# PCB-SSB-4x1.net
KiCad netlist of a schematic drawn in EAGLE
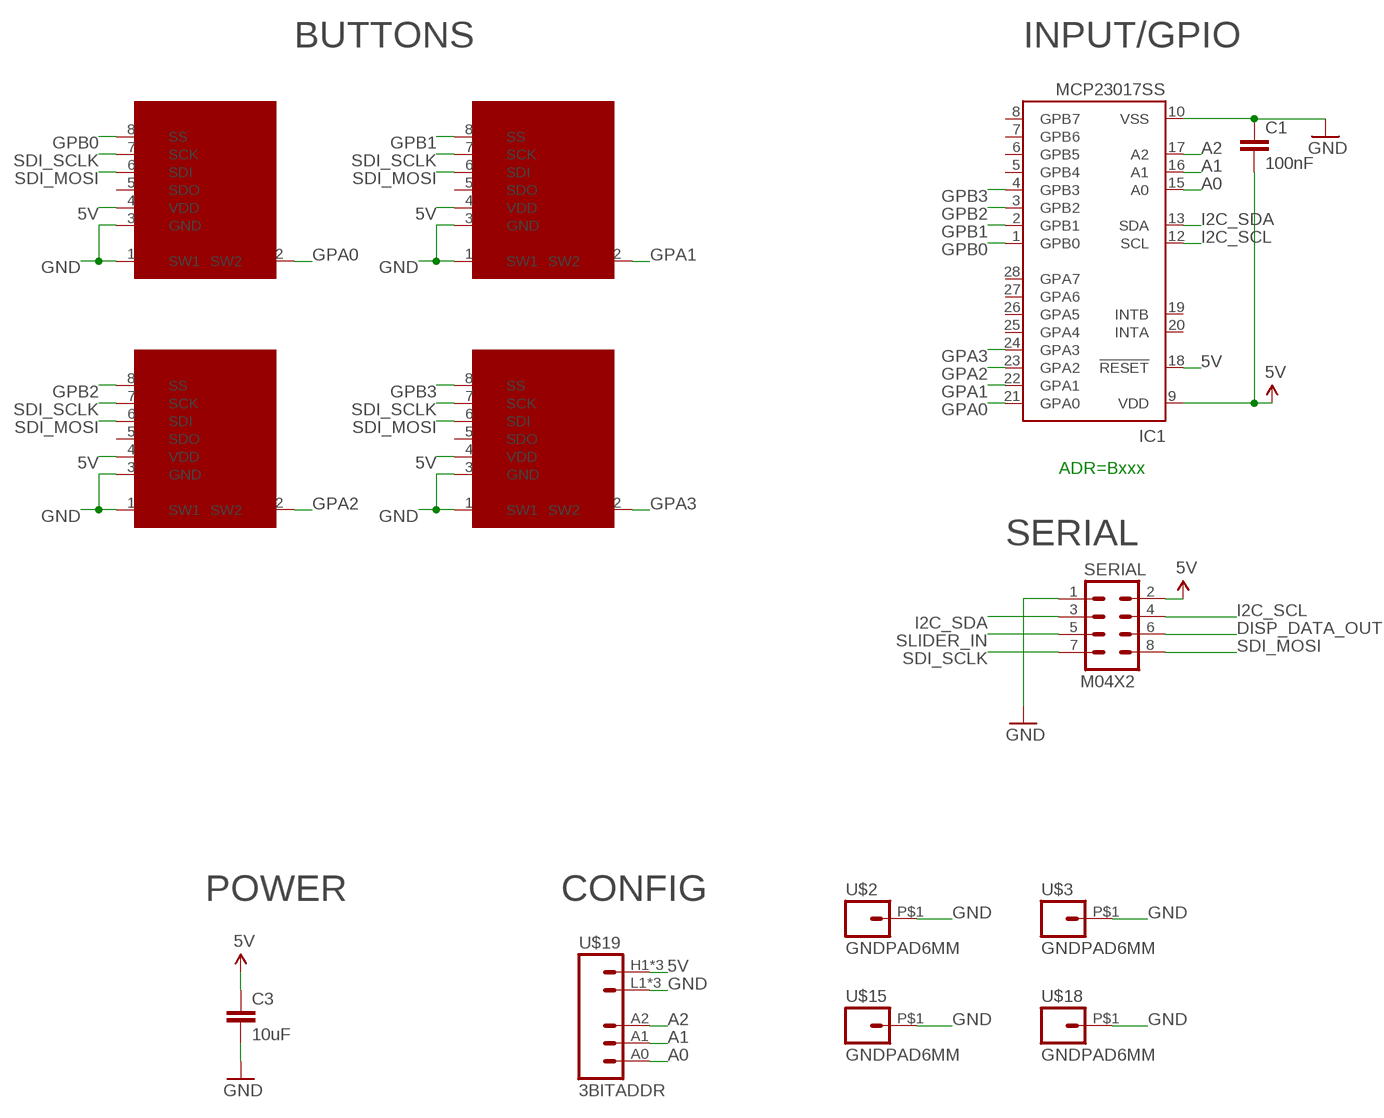
[diagram p0: schematic, sheet 1]

(export (version "E")
  (design (tool "Eeschema 10.0.6"))
  (components
    (comp (ref "C1")
      (value "100nF")
      (footprint "eagle-import:0603-CAP")
      (libsource (lib "eagle-import") (part "CAP0603-CAP"))
    )
    (comp (ref "C3")
      (value "10uF")
      (footprint "eagle-import:0805")
      (libsource (lib "eagle-import") (part "CAP0805"))
    )
    (comp (ref "IC1")
      (value "MCP23017SS")
      (footprint "eagle-import:SSOP28")
      (fields
        (field (name "MF") "MICROCHIP")
        (field (name "MPN") "MCP23017-E/SS")
        (field (name "MPN_1") "MCP23017-E/SS")
        (field (name "OC_FARNELL") "1467674")
        (field (name "OC_NEWARK") "31K2960")
      )
      (libsource (lib "eagle-import") (part "MCP23017SS"))
    )
    (comp (ref "SERIAL")
      (value "M04X2")
      (footprint "eagle-import:2X4")
      (libsource (lib "eagle-import") (part "M04X2"))
    )
    (comp (ref "SSW1")
      (value "SMART_SWITCHSMART_SWITCH_8PIN")
      (footprint "eagle-import:SMART_SWITCH")
      (libsource (lib "eagle-import") (part "SMART_SWITCHSMART_SWITCH_8PIN"))
    )
    (comp (ref "SSW2")
      (value "SMART_SWITCHSMART_SWITCH_8PIN")
      (footprint "eagle-import:SMART_SWITCH")
      (libsource (lib "eagle-import") (part "SMART_SWITCHSMART_SWITCH_8PIN"))
    )
    (comp (ref "SSW3")
      (value "SMART_SWITCHSMART_SWITCH_8PIN")
      (footprint "eagle-import:SMART_SWITCH")
      (libsource (lib "eagle-import") (part "SMART_SWITCHSMART_SWITCH_8PIN"))
    )
    (comp (ref "SSW4")
      (value "SMART_SWITCHSMART_SWITCH_8PIN")
      (footprint "eagle-import:SMART_SWITCH")
      (libsource (lib "eagle-import") (part "SMART_SWITCHSMART_SWITCH_8PIN"))
    )
    (comp (ref "U$2")
      (value "GNDPAD6MM")
      (footprint "eagle-import:3.2MMPAD6MM")
      (libsource (lib "eagle-import") (part "GNDPAD6MM"))
    )
    (comp (ref "U$3")
      (value "GNDPAD6MM")
      (footprint "eagle-import:3.2MMPAD6MM")
      (libsource (lib "eagle-import") (part "GNDPAD6MM"))
    )
    (comp (ref "U$15")
      (value "GNDPAD6MM")
      (footprint "eagle-import:3.2MMPAD6MM")
      (libsource (lib "eagle-import") (part "GNDPAD6MM"))
    )
    (comp (ref "U$18")
      (value "GNDPAD6MM")
      (footprint "eagle-import:3.2MMPAD6MM")
      (libsource (lib "eagle-import") (part "GNDPAD6MM"))
    )
    (comp (ref "U$19")
      (value "3BITADDR")
      (footprint "eagle-import:3BITADDR")
      (libsource (lib "eagle-import") (part "3BITADDR"))
    )
  )
  (nets
    (net (code "1") (name "/A0") (class "Default")
      (node (ref "IC1") (pin "15") (pinfunction "A0_15") (pintype "input"))
      (node (ref "U$19") (pin "A0") (pinfunction "A0_A0") (pintype "passive"))
    )
    (net (code "2") (name "/A1") (class "Default")
      (node (ref "IC1") (pin "16") (pinfunction "A1_16") (pintype "input"))
      (node (ref "U$19") (pin "A1") (pinfunction "A1_A1") (pintype "passive"))
    )
    (net (code "3") (name "/A2") (class "Default")
      (node (ref "IC1") (pin "17") (pinfunction "A2_17") (pintype "input"))
      (node (ref "U$19") (pin "A2") (pinfunction "A2_A2") (pintype "passive"))
    )
    (net (code "4") (name "/DISP_DATA_OUT") (class "Default")
      (node (ref "SERIAL") (pin "6") (pinfunction "6_6") (pintype "passive"))
    )
    (net (code "5") (name "/GPA0") (class "Default")
      (node (ref "IC1") (pin "21") (pinfunction "GPA0_21") (pintype "bidirectional"))
      (node (ref "SSW1") (pin "2") (pinfunction "SW2_2") (pintype "bidirectional"))
    )
    (net (code "6") (name "/GPA1") (class "Default")
      (node (ref "IC1") (pin "22") (pinfunction "GPA1_22") (pintype "bidirectional"))
      (node (ref "SSW2") (pin "2") (pinfunction "SW2_2") (pintype "bidirectional"))
    )
    (net (code "7") (name "/GPA2") (class "Default")
      (node (ref "IC1") (pin "23") (pinfunction "GPA2_23") (pintype "bidirectional"))
      (node (ref "SSW3") (pin "2") (pinfunction "SW2_2") (pintype "bidirectional"))
    )
    (net (code "8") (name "/GPA3") (class "Default")
      (node (ref "IC1") (pin "24") (pinfunction "GPA3_24") (pintype "bidirectional"))
      (node (ref "SSW4") (pin "2") (pinfunction "SW2_2") (pintype "bidirectional"))
    )
    (net (code "9") (name "/GPB0") (class "Default")
      (node (ref "IC1") (pin "1") (pinfunction "GPB0_1") (pintype "bidirectional"))
      (node (ref "SSW1") (pin "8") (pinfunction "SS_8") (pintype "bidirectional"))
    )
    (net (code "10") (name "/GPB1") (class "Default")
      (node (ref "IC1") (pin "2") (pinfunction "GPB1_2") (pintype "bidirectional"))
      (node (ref "SSW2") (pin "8") (pinfunction "SS_8") (pintype "bidirectional"))
    )
    (net (code "11") (name "/GPB2") (class "Default")
      (node (ref "IC1") (pin "3") (pinfunction "GPB2_3") (pintype "bidirectional"))
      (node (ref "SSW3") (pin "8") (pinfunction "SS_8") (pintype "bidirectional"))
    )
    (net (code "12") (name "/GPB3") (class "Default")
      (node (ref "IC1") (pin "4") (pinfunction "GPB3_4") (pintype "bidirectional"))
      (node (ref "SSW4") (pin "8") (pinfunction "SS_8") (pintype "bidirectional"))
    )
    (net (code "13") (name "/I2C_SCL") (class "Default")
      (node (ref "IC1") (pin "12") (pinfunction "SCL_12") (pintype "input"))
      (node (ref "SERIAL") (pin "4") (pinfunction "4_4") (pintype "passive"))
    )
    (net (code "14") (name "/I2C_SDA") (class "Default")
      (node (ref "IC1") (pin "13") (pinfunction "SDA_13") (pintype "bidirectional"))
      (node (ref "SERIAL") (pin "3") (pinfunction "3_3") (pintype "passive"))
    )
    (net (code "15") (name "/SDI_MOSI") (class "Default")
      (node (ref "SERIAL") (pin "8") (pinfunction "8_8") (pintype "passive"))
      (node (ref "SSW1") (pin "6") (pinfunction "SDI_6") (pintype "bidirectional"))
      (node (ref "SSW2") (pin "6") (pinfunction "SDI_6") (pintype "bidirectional"))
      (node (ref "SSW3") (pin "6") (pinfunction "SDI_6") (pintype "bidirectional"))
      (node (ref "SSW4") (pin "6") (pinfunction "SDI_6") (pintype "bidirectional"))
    )
    (net (code "16") (name "/SDI_SCLK") (class "Default")
      (node (ref "SERIAL") (pin "7") (pinfunction "7_7") (pintype "passive"))
      (node (ref "SSW1") (pin "7") (pinfunction "SCK_7") (pintype "bidirectional"))
      (node (ref "SSW2") (pin "7") (pinfunction "SCK_7") (pintype "bidirectional"))
      (node (ref "SSW3") (pin "7") (pinfunction "SCK_7") (pintype "bidirectional"))
      (node (ref "SSW4") (pin "7") (pinfunction "SCK_7") (pintype "bidirectional"))
    )
    (net (code "17") (name "/SLIDER_IN") (class "Default")
      (node (ref "SERIAL") (pin "5") (pinfunction "5_5") (pintype "passive"))
    )
    (net (code "18") (name "5V") (class "Default")
      (node (ref "C1") (pin "2") (pinfunction "2_2") (pintype "passive"))
      (node (ref "C3") (pin "1") (pinfunction "1_1") (pintype "passive"))
      (node (ref "IC1") (pin "18") (pinfunction "~{RESET}_18") (pintype "input"))
      (node (ref "IC1") (pin "9") (pinfunction "VDD_9") (pintype "power_in"))
      (node (ref "SERIAL") (pin "2") (pinfunction "2_2") (pintype "passive"))
      (node (ref "SSW1") (pin "4") (pinfunction "VDD_4") (pintype "bidirectional"))
      (node (ref "SSW2") (pin "4") (pinfunction "VDD_4") (pintype "bidirectional"))
      (node (ref "SSW3") (pin "4") (pinfunction "VDD_4") (pintype "bidirectional"))
      (node (ref "SSW4") (pin "4") (pinfunction "VDD_4") (pintype "bidirectional"))
      (node (ref "U$19") (pin "H1") (pinfunction "VCC_H1") (pintype "passive"))
      (node (ref "U$19") (pin "H2") (pinfunction "VCC_H2") (pintype "passive"))
      (node (ref "U$19") (pin "H3") (pinfunction "VCC_H3") (pintype "passive"))
    )
    (net (code "19") (name "GND") (class "Default")
      (node (ref "C1") (pin "1") (pinfunction "1_1") (pintype "passive"))
      (node (ref "C3") (pin "2") (pinfunction "2_2") (pintype "passive"))
      (node (ref "IC1") (pin "10") (pinfunction "VSS_10") (pintype "power_in"))
      (node (ref "SERIAL") (pin "1") (pinfunction "1_1") (pintype "passive"))
      (node (ref "SSW1") (pin "1") (pinfunction "SW1_1") (pintype "bidirectional"))
      (node (ref "SSW1") (pin "3") (pinfunction "GND_3") (pintype "bidirectional"))
      (node (ref "SSW2") (pin "1") (pinfunction "SW1_1") (pintype "bidirectional"))
      (node (ref "SSW2") (pin "3") (pinfunction "GND_3") (pintype "bidirectional"))
      (node (ref "SSW3") (pin "1") (pinfunction "SW1_1") (pintype "bidirectional"))
      (node (ref "SSW3") (pin "3") (pinfunction "GND_3") (pintype "bidirectional"))
      (node (ref "SSW4") (pin "1") (pinfunction "SW1_1") (pintype "bidirectional"))
      (node (ref "SSW4") (pin "3") (pinfunction "GND_3") (pintype "bidirectional"))
      (node (ref "U$15") (pin "P$1") (pinfunction "1_P$1") (pintype "passive"))
      (node (ref "U$18") (pin "P$1") (pinfunction "1_P$1") (pintype "passive"))
      (node (ref "U$19") (pin "L1") (pinfunction "GND_L1") (pintype "passive"))
      (node (ref "U$19") (pin "L2") (pinfunction "GND_L2") (pintype "passive"))
      (node (ref "U$19") (pin "L3") (pinfunction "GND_L3") (pintype "passive"))
      (node (ref "U$2") (pin "P$1") (pinfunction "1_P$1") (pintype "passive"))
      (node (ref "U$3") (pin "P$1") (pinfunction "1_P$1") (pintype "passive"))
    )
    (net (code "20") (name "unconnected-(IC1-GPA4-Pad25)") (class "Default")
      (node (ref "IC1") (pin "25") (pinfunction "GPA4_25") (pintype "bidirectional"))
    )
    (net (code "21") (name "unconnected-(IC1-GPA5-Pad26)") (class "Default")
      (node (ref "IC1") (pin "26") (pinfunction "GPA5_26") (pintype "bidirectional"))
    )
    (net (code "22") (name "unconnected-(IC1-GPA6-Pad27)") (class "Default")
      (node (ref "IC1") (pin "27") (pinfunction "GPA6_27") (pintype "bidirectional"))
    )
    (net (code "23") (name "unconnected-(IC1-GPA7-Pad28)") (class "Default")
      (node (ref "IC1") (pin "28") (pinfunction "GPA7_28") (pintype "bidirectional"))
    )
    (net (code "24") (name "unconnected-(IC1-GPB4-Pad5)") (class "Default")
      (node (ref "IC1") (pin "5") (pinfunction "GPB4_5") (pintype "bidirectional"))
    )
    (net (code "25") (name "unconnected-(IC1-GPB5-Pad6)") (class "Default")
      (node (ref "IC1") (pin "6") (pinfunction "GPB5_6") (pintype "bidirectional"))
    )
    (net (code "26") (name "unconnected-(IC1-GPB6-Pad7)") (class "Default")
      (node (ref "IC1") (pin "7") (pinfunction "GPB6_7") (pintype "bidirectional"))
    )
    (net (code "27") (name "unconnected-(IC1-GPB7-Pad8)") (class "Default")
      (node (ref "IC1") (pin "8") (pinfunction "GPB7_8") (pintype "bidirectional"))
    )
    (net (code "28") (name "unconnected-(IC1-INTA-Pad20)") (class "Default")
      (node (ref "IC1") (pin "20") (pinfunction "INTA_20") (pintype "output"))
    )
    (net (code "29") (name "unconnected-(IC1-INTB-Pad19)") (class "Default")
      (node (ref "IC1") (pin "19") (pinfunction "INTB_19") (pintype "output"))
    )
    (net (code "30") (name "unconnected-(SSW1-SDO-Pad5)") (class "Default")
      (node (ref "SSW1") (pin "5") (pinfunction "SDO_5") (pintype "bidirectional"))
    )
    (net (code "31") (name "unconnected-(SSW2-SDO-Pad5)") (class "Default")
      (node (ref "SSW2") (pin "5") (pinfunction "SDO_5") (pintype "bidirectional"))
    )
    (net (code "32") (name "unconnected-(SSW3-SDO-Pad5)") (class "Default")
      (node (ref "SSW3") (pin "5") (pinfunction "SDO_5") (pintype "bidirectional"))
    )
    (net (code "33") (name "unconnected-(SSW4-SDO-Pad5)") (class "Default")
      (node (ref "SSW4") (pin "5") (pinfunction "SDO_5") (pintype "bidirectional"))
    )
  )
)
